# NUCLEO_UNIVERSAL_BOARD.net
KiCad netlist of a schematic drawn in EAGLE
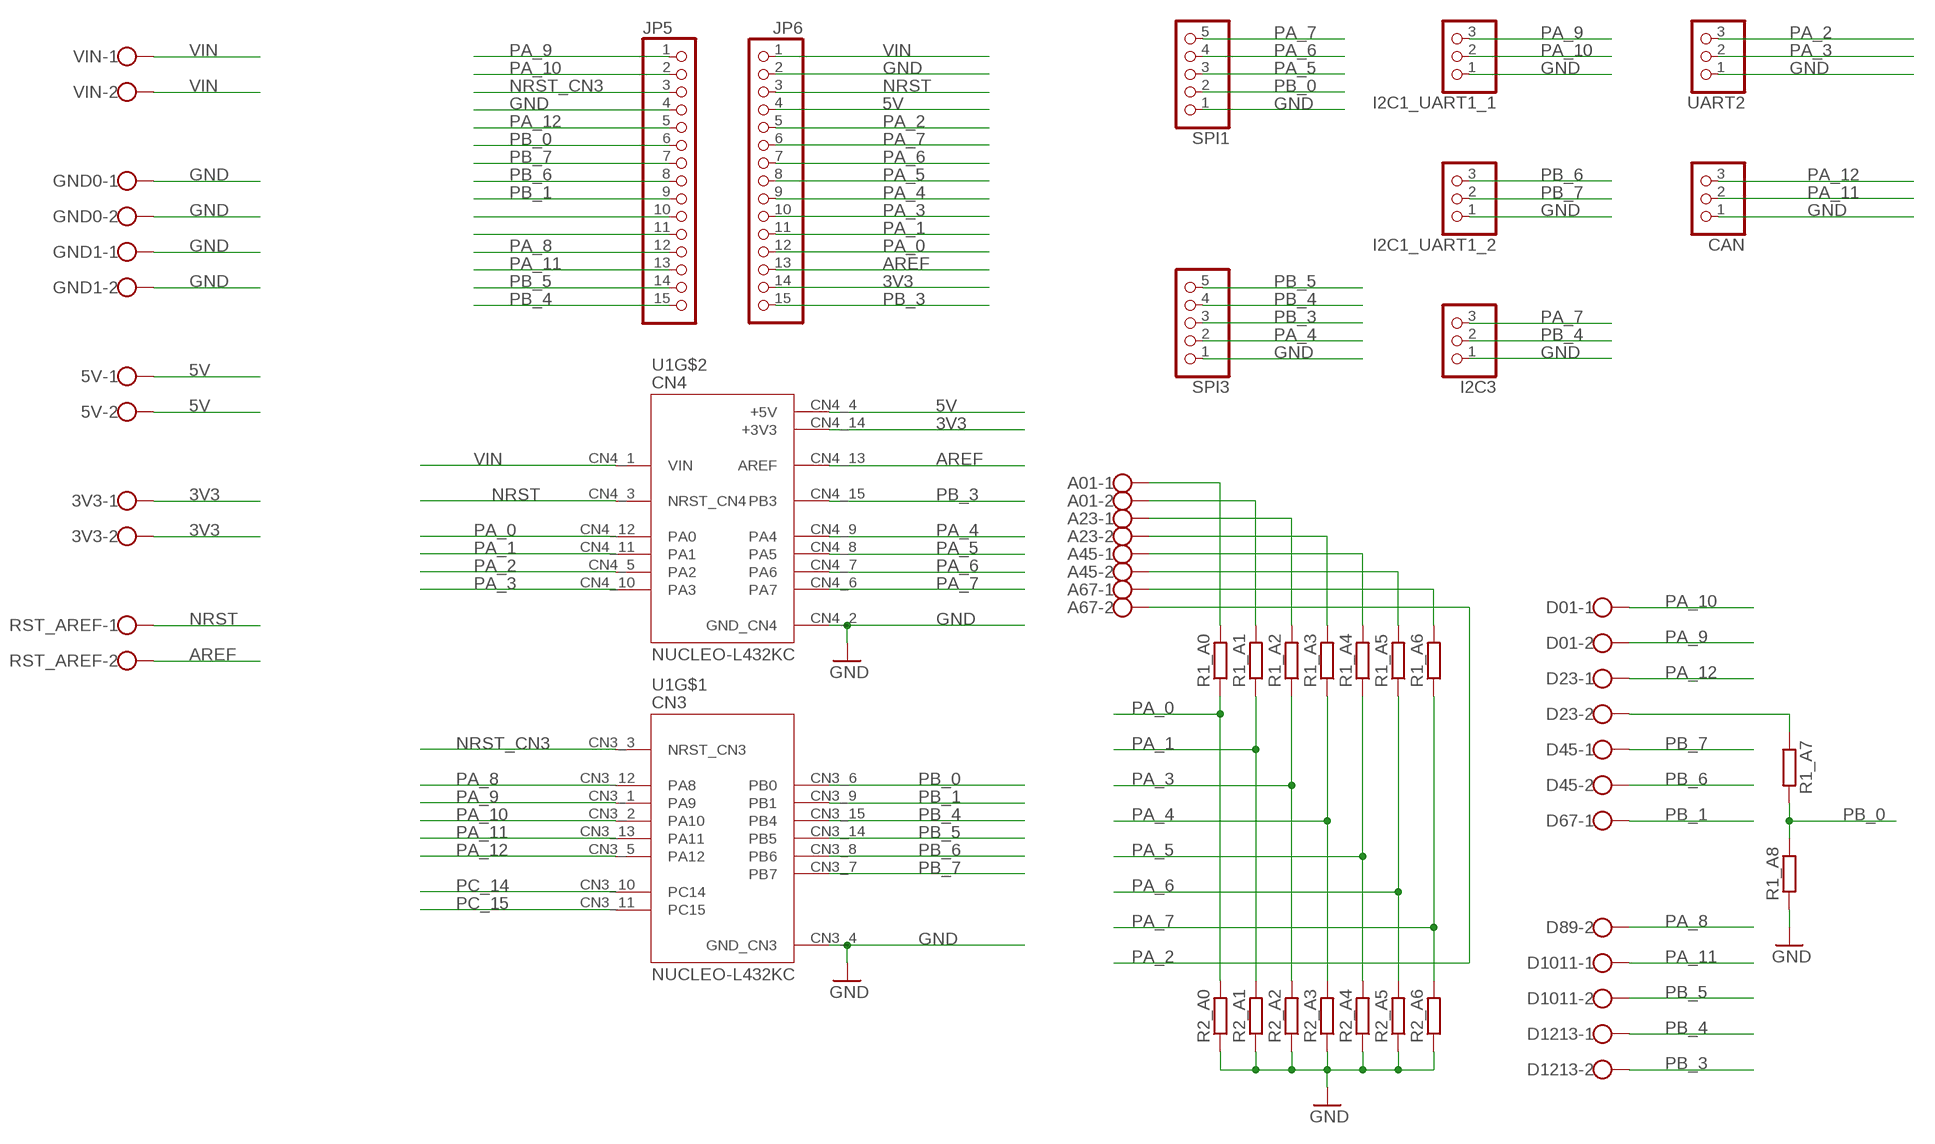
[diagram p0: schematic, sheet 1]

(export (version "E")
  (design (tool "Eeschema 10.0.6"))
  (components
    (comp (ref "3V3")
      (value "W237-102")
      (footprint "eagle-import:W237-102")
      (fields (field (name "MPN") "237-102"))
      (libsource (lib "eagle-import") (part "W237-102"))
    )
    (comp (ref "5V")
      (value "W237-102")
      (footprint "eagle-import:W237-102")
      (fields (field (name "MPN") "237-102"))
      (libsource (lib "eagle-import") (part "W237-102"))
    )
    (comp (ref "A01")
      (value "W237-102")
      (footprint "eagle-import:W237-102")
      (fields (field (name "MPN") "237-102"))
      (libsource (lib "eagle-import") (part "W237-102"))
    )
    (comp (ref "A23")
      (value "W237-102")
      (footprint "eagle-import:W237-102")
      (fields (field (name "MPN") "237-102"))
      (libsource (lib "eagle-import") (part "W237-102"))
    )
    (comp (ref "A45")
      (value "W237-102")
      (footprint "eagle-import:W237-102")
      (fields (field (name "MPN") "237-102"))
      (libsource (lib "eagle-import") (part "W237-102"))
    )
    (comp (ref "A67")
      (value "W237-102")
      (footprint "eagle-import:W237-102")
      (fields (field (name "MPN") "237-102"))
      (libsource (lib "eagle-import") (part "W237-102"))
    )
    (comp (ref "CAN")
      (value "PINHD-1X3")
      (footprint "eagle-import:1X03")
      (libsource (lib "eagle-import") (part "PINHD-1X3"))
    )
    (comp (ref "D01")
      (value "W237-102")
      (footprint "eagle-import:W237-102")
      (fields (field (name "MPN") "237-102"))
      (libsource (lib "eagle-import") (part "W237-102"))
    )
    (comp (ref "D23")
      (value "W237-102")
      (footprint "eagle-import:W237-102")
      (fields (field (name "MPN") "237-102"))
      (libsource (lib "eagle-import") (part "W237-102"))
    )
    (comp (ref "D45")
      (value "W237-102")
      (footprint "eagle-import:W237-102")
      (fields (field (name "MPN") "237-102"))
      (libsource (lib "eagle-import") (part "W237-102"))
    )
    (comp (ref "D67")
      (value "W237-102")
      (footprint "eagle-import:W237-102")
      (fields (field (name "MPN") "237-102"))
      (libsource (lib "eagle-import") (part "W237-102"))
    )
    (comp (ref "D89")
      (value "W237-102")
      (footprint "eagle-import:W237-102")
      (fields (field (name "MPN") "237-102"))
      (libsource (lib "eagle-import") (part "W237-102"))
    )
    (comp (ref "D1011")
      (value "W237-102")
      (footprint "eagle-import:W237-102")
      (fields (field (name "MPN") "237-102"))
      (libsource (lib "eagle-import") (part "W237-102"))
    )
    (comp (ref "D1213")
      (value "W237-102")
      (footprint "eagle-import:W237-102")
      (fields (field (name "MPN") "237-102"))
      (libsource (lib "eagle-import") (part "W237-102"))
    )
    (comp (ref "GND0")
      (value "W237-102")
      (footprint "eagle-import:W237-102")
      (fields (field (name "MPN") "237-102"))
      (libsource (lib "eagle-import") (part "W237-102"))
    )
    (comp (ref "GND1")
      (value "W237-102")
      (footprint "eagle-import:W237-102")
      (fields (field (name "MPN") "237-102"))
      (libsource (lib "eagle-import") (part "W237-102"))
    )
    (comp (ref "I2C1_UART1_1")
      (value "PINHD-1X3")
      (footprint "eagle-import:1X03")
      (libsource (lib "eagle-import") (part "PINHD-1X3"))
    )
    (comp (ref "I2C1_UART1_2")
      (value "PINHD-1X3")
      (footprint "eagle-import:1X03")
      (libsource (lib "eagle-import") (part "PINHD-1X3"))
    )
    (comp (ref "I2C3")
      (value "PINHD-1X3")
      (footprint "eagle-import:1X03")
      (libsource (lib "eagle-import") (part "PINHD-1X3"))
    )
    (comp (ref "JP5")
      (value "PINHD-1X15")
      (footprint "eagle-import:1X15")
      (libsource (lib "eagle-import") (part "PINHD-1X15"))
    )
    (comp (ref "JP6")
      (value "PINHD-1X15")
      (footprint "eagle-import:1X15")
      (libsource (lib "eagle-import") (part "PINHD-1X15"))
    )
    (comp (ref "R1_A0")
      (value "R-EU_M1206")
      (footprint "eagle-import:M1206")
      (libsource (lib "eagle-import") (part "R-EU_M1206"))
    )
    (comp (ref "R1_A1")
      (value "R-EU_M1206")
      (footprint "eagle-import:M1206")
      (libsource (lib "eagle-import") (part "R-EU_M1206"))
    )
    (comp (ref "R1_A2")
      (value "R-EU_M1206")
      (footprint "eagle-import:M1206")
      (libsource (lib "eagle-import") (part "R-EU_M1206"))
    )
    (comp (ref "R1_A3")
      (value "R-EU_M1206")
      (footprint "eagle-import:M1206")
      (libsource (lib "eagle-import") (part "R-EU_M1206"))
    )
    (comp (ref "R1_A4")
      (value "R-EU_M1206")
      (footprint "eagle-import:M1206")
      (libsource (lib "eagle-import") (part "R-EU_M1206"))
    )
    (comp (ref "R1_A5")
      (value "R-EU_M1206")
      (footprint "eagle-import:M1206")
      (libsource (lib "eagle-import") (part "R-EU_M1206"))
    )
    (comp (ref "R1_A6")
      (value "R-EU_M1206")
      (footprint "eagle-import:M1206")
      (libsource (lib "eagle-import") (part "R-EU_M1206"))
    )
    (comp (ref "R1_A7")
      (value "R-EU_M1206")
      (footprint "eagle-import:M1206")
      (libsource (lib "eagle-import") (part "R-EU_M1206"))
    )
    (comp (ref "R1_A8")
      (value "R-EU_M1206")
      (footprint "eagle-import:M1206")
      (libsource (lib "eagle-import") (part "R-EU_M1206"))
    )
    (comp (ref "R2_A0")
      (value "R-EU_M1206")
      (footprint "eagle-import:M1206")
      (libsource (lib "eagle-import") (part "R-EU_M1206"))
    )
    (comp (ref "R2_A1")
      (value "R-EU_M1206")
      (footprint "eagle-import:M1206")
      (libsource (lib "eagle-import") (part "R-EU_M1206"))
    )
    (comp (ref "R2_A2")
      (value "R-EU_M1206")
      (footprint "eagle-import:M1206")
      (libsource (lib "eagle-import") (part "R-EU_M1206"))
    )
    (comp (ref "R2_A3")
      (value "R-EU_M1206")
      (footprint "eagle-import:M1206")
      (libsource (lib "eagle-import") (part "R-EU_M1206"))
    )
    (comp (ref "R2_A4")
      (value "R-EU_M1206")
      (footprint "eagle-import:M1206")
      (libsource (lib "eagle-import") (part "R-EU_M1206"))
    )
    (comp (ref "R2_A5")
      (value "R-EU_M1206")
      (footprint "eagle-import:M1206")
      (libsource (lib "eagle-import") (part "R-EU_M1206"))
    )
    (comp (ref "R2_A6")
      (value "R-EU_M1206")
      (footprint "eagle-import:M1206")
      (libsource (lib "eagle-import") (part "R-EU_M1206"))
    )
    (comp (ref "RST_AREF")
      (value "W237-102")
      (footprint "eagle-import:W237-102")
      (fields (field (name "MPN") "237-102"))
      (libsource (lib "eagle-import") (part "W237-102"))
    )
    (comp (ref "SPI1")
      (value "PINHD-1X5")
      (footprint "eagle-import:1X05")
      (libsource (lib "eagle-import") (part "PINHD-1X5"))
    )
    (comp (ref "SPI3")
      (value "PINHD-1X5")
      (footprint "eagle-import:1X05")
      (libsource (lib "eagle-import") (part "PINHD-1X5"))
    )
    (comp (ref "U1")
      (value "NUCLEO-L432KC")
      (footprint "eagle-import:MODULE_NUCLEO-L432KC")
      (fields (field (name "MF") "STMicroelectronics"))
      (libsource (lib "eagle-import") (part "NUCLEO-L432KC"))
    )
    (comp (ref "UART2")
      (value "PINHD-1X3")
      (footprint "eagle-import:1X03")
      (libsource (lib "eagle-import") (part "PINHD-1X3"))
    )
    (comp (ref "VIN")
      (value "W237-102")
      (footprint "eagle-import:W237-102")
      (fields (field (name "MPN") "237-102"))
      (libsource (lib "eagle-import") (part "W237-102"))
    )
  )
  (nets
    (net (code "1") (name "/3V3") (class "Default")
      (node (ref "3V3") (pin "1") (pinfunction "KL_1") (pintype "passive"))
      (node (ref "3V3") (pin "2") (pinfunction "KL_2") (pintype "passive"))
      (node (ref "JP6") (pin "14") (pinfunction "14_14") (pintype "passive"))
      (node (ref "U1") (pin "CN4_14") (pinfunction "+3V3_CN4_14") (pintype "power_in"))
    )
    (net (code "2") (name "/5V") (class "Default")
      (node (ref "5V") (pin "1") (pinfunction "KL_1") (pintype "passive"))
      (node (ref "5V") (pin "2") (pinfunction "KL_2") (pintype "passive"))
      (node (ref "JP6") (pin "4") (pinfunction "4_4") (pintype "passive"))
      (node (ref "U1") (pin "CN4_4") (pinfunction "+5V_CN4_4") (pintype "power_in"))
    )
    (net (code "3") (name "/AREF") (class "Default")
      (node (ref "JP6") (pin "13") (pinfunction "13_13") (pintype "passive"))
      (node (ref "RST_AREF") (pin "2") (pinfunction "KL_2") (pintype "passive"))
      (node (ref "U1") (pin "CN4_13") (pinfunction "AREF_CN4_13") (pintype "bidirectional"))
    )
    (net (code "4") (name "/NRST") (class "Default")
      (node (ref "JP6") (pin "3") (pinfunction "3_3") (pintype "passive"))
      (node (ref "RST_AREF") (pin "1") (pinfunction "KL_1") (pintype "passive"))
      (node (ref "U1") (pin "CN4_3") (pinfunction "NRST_CN4_CN4_3") (pintype "bidirectional"))
    )
    (net (code "5") (name "/NRST_CN3") (class "Default")
      (node (ref "JP5") (pin "3") (pinfunction "3_3") (pintype "passive"))
      (node (ref "U1") (pin "CN3_3") (pinfunction "NRST_CN3_CN3_3") (pintype "bidirectional"))
    )
    (net (code "6") (name "/PA_0") (class "Default")
      (node (ref "JP6") (pin "12") (pinfunction "12_12") (pintype "passive"))
      (node (ref "R1_A0") (pin "1") (pinfunction "1_1") (pintype "passive"))
      (node (ref "R2_A0") (pin "2") (pinfunction "2_2") (pintype "passive"))
      (node (ref "U1") (pin "CN4_12") (pinfunction "PA0_CN4_12") (pintype "bidirectional"))
    )
    (net (code "7") (name "/PA_1") (class "Default")
      (node (ref "JP6") (pin "11") (pinfunction "11_11") (pintype "passive"))
      (node (ref "R1_A1") (pin "1") (pinfunction "1_1") (pintype "passive"))
      (node (ref "R2_A1") (pin "2") (pinfunction "2_2") (pintype "passive"))
      (node (ref "U1") (pin "CN4_11") (pinfunction "PA1_CN4_11") (pintype "bidirectional"))
    )
    (net (code "8") (name "/PA_2") (class "Default")
      (node (ref "A67") (pin "2") (pinfunction "KL_2") (pintype "passive"))
      (node (ref "JP6") (pin "5") (pinfunction "5_5") (pintype "passive"))
      (node (ref "U1") (pin "CN4_5") (pinfunction "PA2_CN4_5") (pintype "bidirectional"))
      (node (ref "UART2") (pin "3") (pinfunction "3_3") (pintype "passive"))
    )
    (net (code "9") (name "/PA_3") (class "Default")
      (node (ref "JP6") (pin "10") (pinfunction "10_10") (pintype "passive"))
      (node (ref "R1_A2") (pin "1") (pinfunction "1_1") (pintype "passive"))
      (node (ref "R2_A2") (pin "2") (pinfunction "2_2") (pintype "passive"))
      (node (ref "U1") (pin "CN4_10") (pinfunction "PA3_CN4_10") (pintype "bidirectional"))
      (node (ref "UART2") (pin "2") (pinfunction "2_2") (pintype "passive"))
    )
    (net (code "10") (name "/PA_4") (class "Default")
      (node (ref "JP6") (pin "9") (pinfunction "9_9") (pintype "passive"))
      (node (ref "R1_A3") (pin "1") (pinfunction "1_1") (pintype "passive"))
      (node (ref "R2_A3") (pin "2") (pinfunction "2_2") (pintype "passive"))
      (node (ref "SPI3") (pin "2") (pinfunction "2_2") (pintype "passive"))
      (node (ref "U1") (pin "CN4_9") (pinfunction "PA4_CN4_9") (pintype "bidirectional"))
    )
    (net (code "11") (name "/PA_5") (class "Default")
      (node (ref "JP6") (pin "8") (pinfunction "8_8") (pintype "passive"))
      (node (ref "R1_A4") (pin "1") (pinfunction "1_1") (pintype "passive"))
      (node (ref "R2_A4") (pin "2") (pinfunction "2_2") (pintype "passive"))
      (node (ref "SPI1") (pin "3") (pinfunction "3_3") (pintype "passive"))
      (node (ref "U1") (pin "CN4_8") (pinfunction "PA5_CN4_8") (pintype "bidirectional"))
    )
    (net (code "12") (name "/PA_6") (class "Default")
      (node (ref "JP6") (pin "7") (pinfunction "7_7") (pintype "passive"))
      (node (ref "R1_A5") (pin "1") (pinfunction "1_1") (pintype "passive"))
      (node (ref "R2_A5") (pin "2") (pinfunction "2_2") (pintype "passive"))
      (node (ref "SPI1") (pin "4") (pinfunction "4_4") (pintype "passive"))
      (node (ref "U1") (pin "CN4_7") (pinfunction "PA6_CN4_7") (pintype "bidirectional"))
    )
    (net (code "13") (name "/PA_7") (class "Default")
      (node (ref "I2C3") (pin "3") (pinfunction "3_3") (pintype "passive"))
      (node (ref "JP6") (pin "6") (pinfunction "6_6") (pintype "passive"))
      (node (ref "R1_A6") (pin "1") (pinfunction "1_1") (pintype "passive"))
      (node (ref "R2_A6") (pin "2") (pinfunction "2_2") (pintype "passive"))
      (node (ref "SPI1") (pin "5") (pinfunction "5_5") (pintype "passive"))
      (node (ref "U1") (pin "CN4_6") (pinfunction "PA7_CN4_6") (pintype "bidirectional"))
    )
    (net (code "14") (name "/PA_8") (class "Default")
      (node (ref "D89") (pin "2") (pinfunction "KL_2") (pintype "passive"))
      (node (ref "JP5") (pin "12") (pinfunction "12_12") (pintype "passive"))
      (node (ref "U1") (pin "CN3_12") (pinfunction "PA8_CN3_12") (pintype "bidirectional"))
    )
    (net (code "15") (name "/PA_9") (class "Default")
      (node (ref "D01") (pin "2") (pinfunction "KL_2") (pintype "passive"))
      (node (ref "I2C1_UART1_1") (pin "3") (pinfunction "3_3") (pintype "passive"))
      (node (ref "JP5") (pin "1") (pinfunction "1_1") (pintype "passive"))
      (node (ref "U1") (pin "CN3_1") (pinfunction "PA9_CN3_1") (pintype "bidirectional"))
    )
    (net (code "16") (name "/PA_10") (class "Default")
      (node (ref "D01") (pin "1") (pinfunction "KL_1") (pintype "passive"))
      (node (ref "I2C1_UART1_1") (pin "2") (pinfunction "2_2") (pintype "passive"))
      (node (ref "JP5") (pin "2") (pinfunction "2_2") (pintype "passive"))
      (node (ref "U1") (pin "CN3_2") (pinfunction "PA10_CN3_2") (pintype "bidirectional"))
    )
    (net (code "17") (name "/PA_11") (class "Default")
      (node (ref "CAN") (pin "2") (pinfunction "2_2") (pintype "passive"))
      (node (ref "D1011") (pin "1") (pinfunction "KL_1") (pintype "passive"))
      (node (ref "JP5") (pin "13") (pinfunction "13_13") (pintype "passive"))
      (node (ref "U1") (pin "CN3_13") (pinfunction "PA11_CN3_13") (pintype "bidirectional"))
    )
    (net (code "18") (name "/PA_12") (class "Default")
      (node (ref "CAN") (pin "3") (pinfunction "3_3") (pintype "passive"))
      (node (ref "D23") (pin "1") (pinfunction "KL_1") (pintype "passive"))
      (node (ref "JP5") (pin "5") (pinfunction "5_5") (pintype "passive"))
      (node (ref "U1") (pin "CN3_5") (pinfunction "PA12_CN3_5") (pintype "bidirectional"))
    )
    (net (code "19") (name "/PB_0") (class "Default")
      (node (ref "JP5") (pin "6") (pinfunction "6_6") (pintype "passive"))
      (node (ref "R1_A7") (pin "2") (pinfunction "2_2") (pintype "passive"))
      (node (ref "R1_A8") (pin "2") (pinfunction "2_2") (pintype "passive"))
      (node (ref "SPI1") (pin "2") (pinfunction "2_2") (pintype "passive"))
      (node (ref "U1") (pin "CN3_6") (pinfunction "PB0_CN3_6") (pintype "bidirectional"))
    )
    (net (code "20") (name "/PB_1") (class "Default")
      (node (ref "D67") (pin "1") (pinfunction "KL_1") (pintype "passive"))
      (node (ref "JP5") (pin "9") (pinfunction "9_9") (pintype "passive"))
      (node (ref "U1") (pin "CN3_9") (pinfunction "PB1_CN3_9") (pintype "bidirectional"))
    )
    (net (code "21") (name "/PB_3") (class "Default")
      (node (ref "D1213") (pin "2") (pinfunction "KL_2") (pintype "passive"))
      (node (ref "JP6") (pin "15") (pinfunction "15_15") (pintype "passive"))
      (node (ref "SPI3") (pin "3") (pinfunction "3_3") (pintype "passive"))
      (node (ref "U1") (pin "CN4_15") (pinfunction "PB3_CN4_15") (pintype "bidirectional"))
    )
    (net (code "22") (name "/PB_4") (class "Default")
      (node (ref "D1213") (pin "1") (pinfunction "KL_1") (pintype "passive"))
      (node (ref "I2C3") (pin "2") (pinfunction "2_2") (pintype "passive"))
      (node (ref "JP5") (pin "15") (pinfunction "15_15") (pintype "passive"))
      (node (ref "SPI3") (pin "4") (pinfunction "4_4") (pintype "passive"))
      (node (ref "U1") (pin "CN3_15") (pinfunction "PB4_CN3_15") (pintype "bidirectional"))
    )
    (net (code "23") (name "/PB_5") (class "Default")
      (node (ref "D1011") (pin "2") (pinfunction "KL_2") (pintype "passive"))
      (node (ref "JP5") (pin "14") (pinfunction "14_14") (pintype "passive"))
      (node (ref "SPI3") (pin "5") (pinfunction "5_5") (pintype "passive"))
      (node (ref "U1") (pin "CN3_14") (pinfunction "PB5_CN3_14") (pintype "bidirectional"))
    )
    (net (code "24") (name "/PB_6") (class "Default")
      (node (ref "D45") (pin "2") (pinfunction "KL_2") (pintype "passive"))
      (node (ref "I2C1_UART1_2") (pin "3") (pinfunction "3_3") (pintype "passive"))
      (node (ref "JP5") (pin "8") (pinfunction "8_8") (pintype "passive"))
      (node (ref "U1") (pin "CN3_8") (pinfunction "PB6_CN3_8") (pintype "bidirectional"))
    )
    (net (code "25") (name "/PB_7") (class "Default")
      (node (ref "D45") (pin "1") (pinfunction "KL_1") (pintype "passive"))
      (node (ref "I2C1_UART1_2") (pin "2") (pinfunction "2_2") (pintype "passive"))
      (node (ref "JP5") (pin "7") (pinfunction "7_7") (pintype "passive"))
      (node (ref "U1") (pin "CN3_7") (pinfunction "PB7_CN3_7") (pintype "bidirectional"))
    )
    (net (code "26") (name "/PC_14") (class "Default")
      (node (ref "U1") (pin "CN3_10") (pinfunction "PC14_CN3_10") (pintype "bidirectional"))
    )
    (net (code "27") (name "/PC_15") (class "Default")
      (node (ref "U1") (pin "CN3_11") (pinfunction "PC15_CN3_11") (pintype "bidirectional"))
    )
    (net (code "28") (name "/VIN") (class "Default")
      (node (ref "JP6") (pin "1") (pinfunction "1_1") (pintype "passive"))
      (node (ref "U1") (pin "CN4_1") (pinfunction "VIN_CN4_1") (pintype "input"))
      (node (ref "VIN") (pin "1") (pinfunction "KL_1") (pintype "passive"))
      (node (ref "VIN") (pin "2") (pinfunction "KL_2") (pintype "passive"))
    )
    (net (code "29") (name "GND") (class "Default")
      (node (ref "CAN") (pin "1") (pinfunction "1_1") (pintype "passive"))
      (node (ref "GND0") (pin "1") (pinfunction "KL_1") (pintype "passive"))
      (node (ref "GND0") (pin "2") (pinfunction "KL_2") (pintype "passive"))
      (node (ref "GND1") (pin "1") (pinfunction "KL_1") (pintype "passive"))
      (node (ref "GND1") (pin "2") (pinfunction "KL_2") (pintype "passive"))
      (node (ref "I2C1_UART1_1") (pin "1") (pinfunction "1_1") (pintype "passive"))
      (node (ref "I2C1_UART1_2") (pin "1") (pinfunction "1_1") (pintype "passive"))
      (node (ref "I2C3") (pin "1") (pinfunction "1_1") (pintype "passive"))
      (node (ref "JP5") (pin "4") (pinfunction "4_4") (pintype "passive"))
      (node (ref "JP6") (pin "2") (pinfunction "2_2") (pintype "passive"))
      (node (ref "R1_A8") (pin "1") (pinfunction "1_1") (pintype "passive"))
      (node (ref "R2_A0") (pin "1") (pinfunction "1_1") (pintype "passive"))
      (node (ref "R2_A1") (pin "1") (pinfunction "1_1") (pintype "passive"))
      (node (ref "R2_A2") (pin "1") (pinfunction "1_1") (pintype "passive"))
      (node (ref "R2_A3") (pin "1") (pinfunction "1_1") (pintype "passive"))
      (node (ref "R2_A4") (pin "1") (pinfunction "1_1") (pintype "passive"))
      (node (ref "R2_A5") (pin "1") (pinfunction "1_1") (pintype "passive"))
      (node (ref "R2_A6") (pin "1") (pinfunction "1_1") (pintype "passive"))
      (node (ref "SPI1") (pin "1") (pinfunction "1_1") (pintype "passive"))
      (node (ref "SPI3") (pin "1") (pinfunction "1_1") (pintype "passive"))
      (node (ref "U1") (pin "CN3_4") (pinfunction "GND_CN3_CN3_4") (pintype "power_in"))
      (node (ref "U1") (pin "CN4_2") (pinfunction "GND_CN4_CN4_2") (pintype "power_in"))
      (node (ref "UART2") (pin "1") (pinfunction "1_1") (pintype "passive"))
    )
    (net (code "30") (name "Net-(A01A-KL)") (class "Default")
      (node (ref "A01") (pin "1") (pinfunction "KL_1") (pintype "passive"))
      (node (ref "R1_A0") (pin "2") (pinfunction "2_2") (pintype "passive"))
    )
    (net (code "31") (name "Net-(A01B-KL)") (class "Default")
      (node (ref "A01") (pin "2") (pinfunction "KL_2") (pintype "passive"))
      (node (ref "R1_A1") (pin "2") (pinfunction "2_2") (pintype "passive"))
    )
    (net (code "32") (name "Net-(A23A-KL)") (class "Default")
      (node (ref "A23") (pin "1") (pinfunction "KL_1") (pintype "passive"))
      (node (ref "R1_A2") (pin "2") (pinfunction "2_2") (pintype "passive"))
    )
    (net (code "33") (name "Net-(A23B-KL)") (class "Default")
      (node (ref "A23") (pin "2") (pinfunction "KL_2") (pintype "passive"))
      (node (ref "R1_A3") (pin "2") (pinfunction "2_2") (pintype "passive"))
    )
    (net (code "34") (name "Net-(A45A-KL)") (class "Default")
      (node (ref "A45") (pin "1") (pinfunction "KL_1") (pintype "passive"))
      (node (ref "R1_A4") (pin "2") (pinfunction "2_2") (pintype "passive"))
    )
    (net (code "35") (name "Net-(A45B-KL)") (class "Default")
      (node (ref "A45") (pin "2") (pinfunction "KL_2") (pintype "passive"))
      (node (ref "R1_A5") (pin "2") (pinfunction "2_2") (pintype "passive"))
    )
    (net (code "36") (name "Net-(A67A-KL)") (class "Default")
      (node (ref "A67") (pin "1") (pinfunction "KL_1") (pintype "passive"))
      (node (ref "R1_A6") (pin "2") (pinfunction "2_2") (pintype "passive"))
    )
    (net (code "37") (name "Net-(D23B-KL)") (class "Default")
      (node (ref "D23") (pin "2") (pinfunction "KL_2") (pintype "passive"))
      (node (ref "R1_A7") (pin "1") (pinfunction "1_1") (pintype "passive"))
    )
    (net (code "38") (name "unconnected-(JP5-Pad10)") (class "Default")
      (node (ref "JP5") (pin "10") (pinfunction "10_10") (pintype "passive"))
    )
    (net (code "39") (name "unconnected-(JP5-Pad11)") (class "Default")
      (node (ref "JP5") (pin "11") (pinfunction "11_11") (pintype "passive"))
    )
  )
)
